# Mainboard.net
KiCad netlist of a schematic drawn in EAGLE
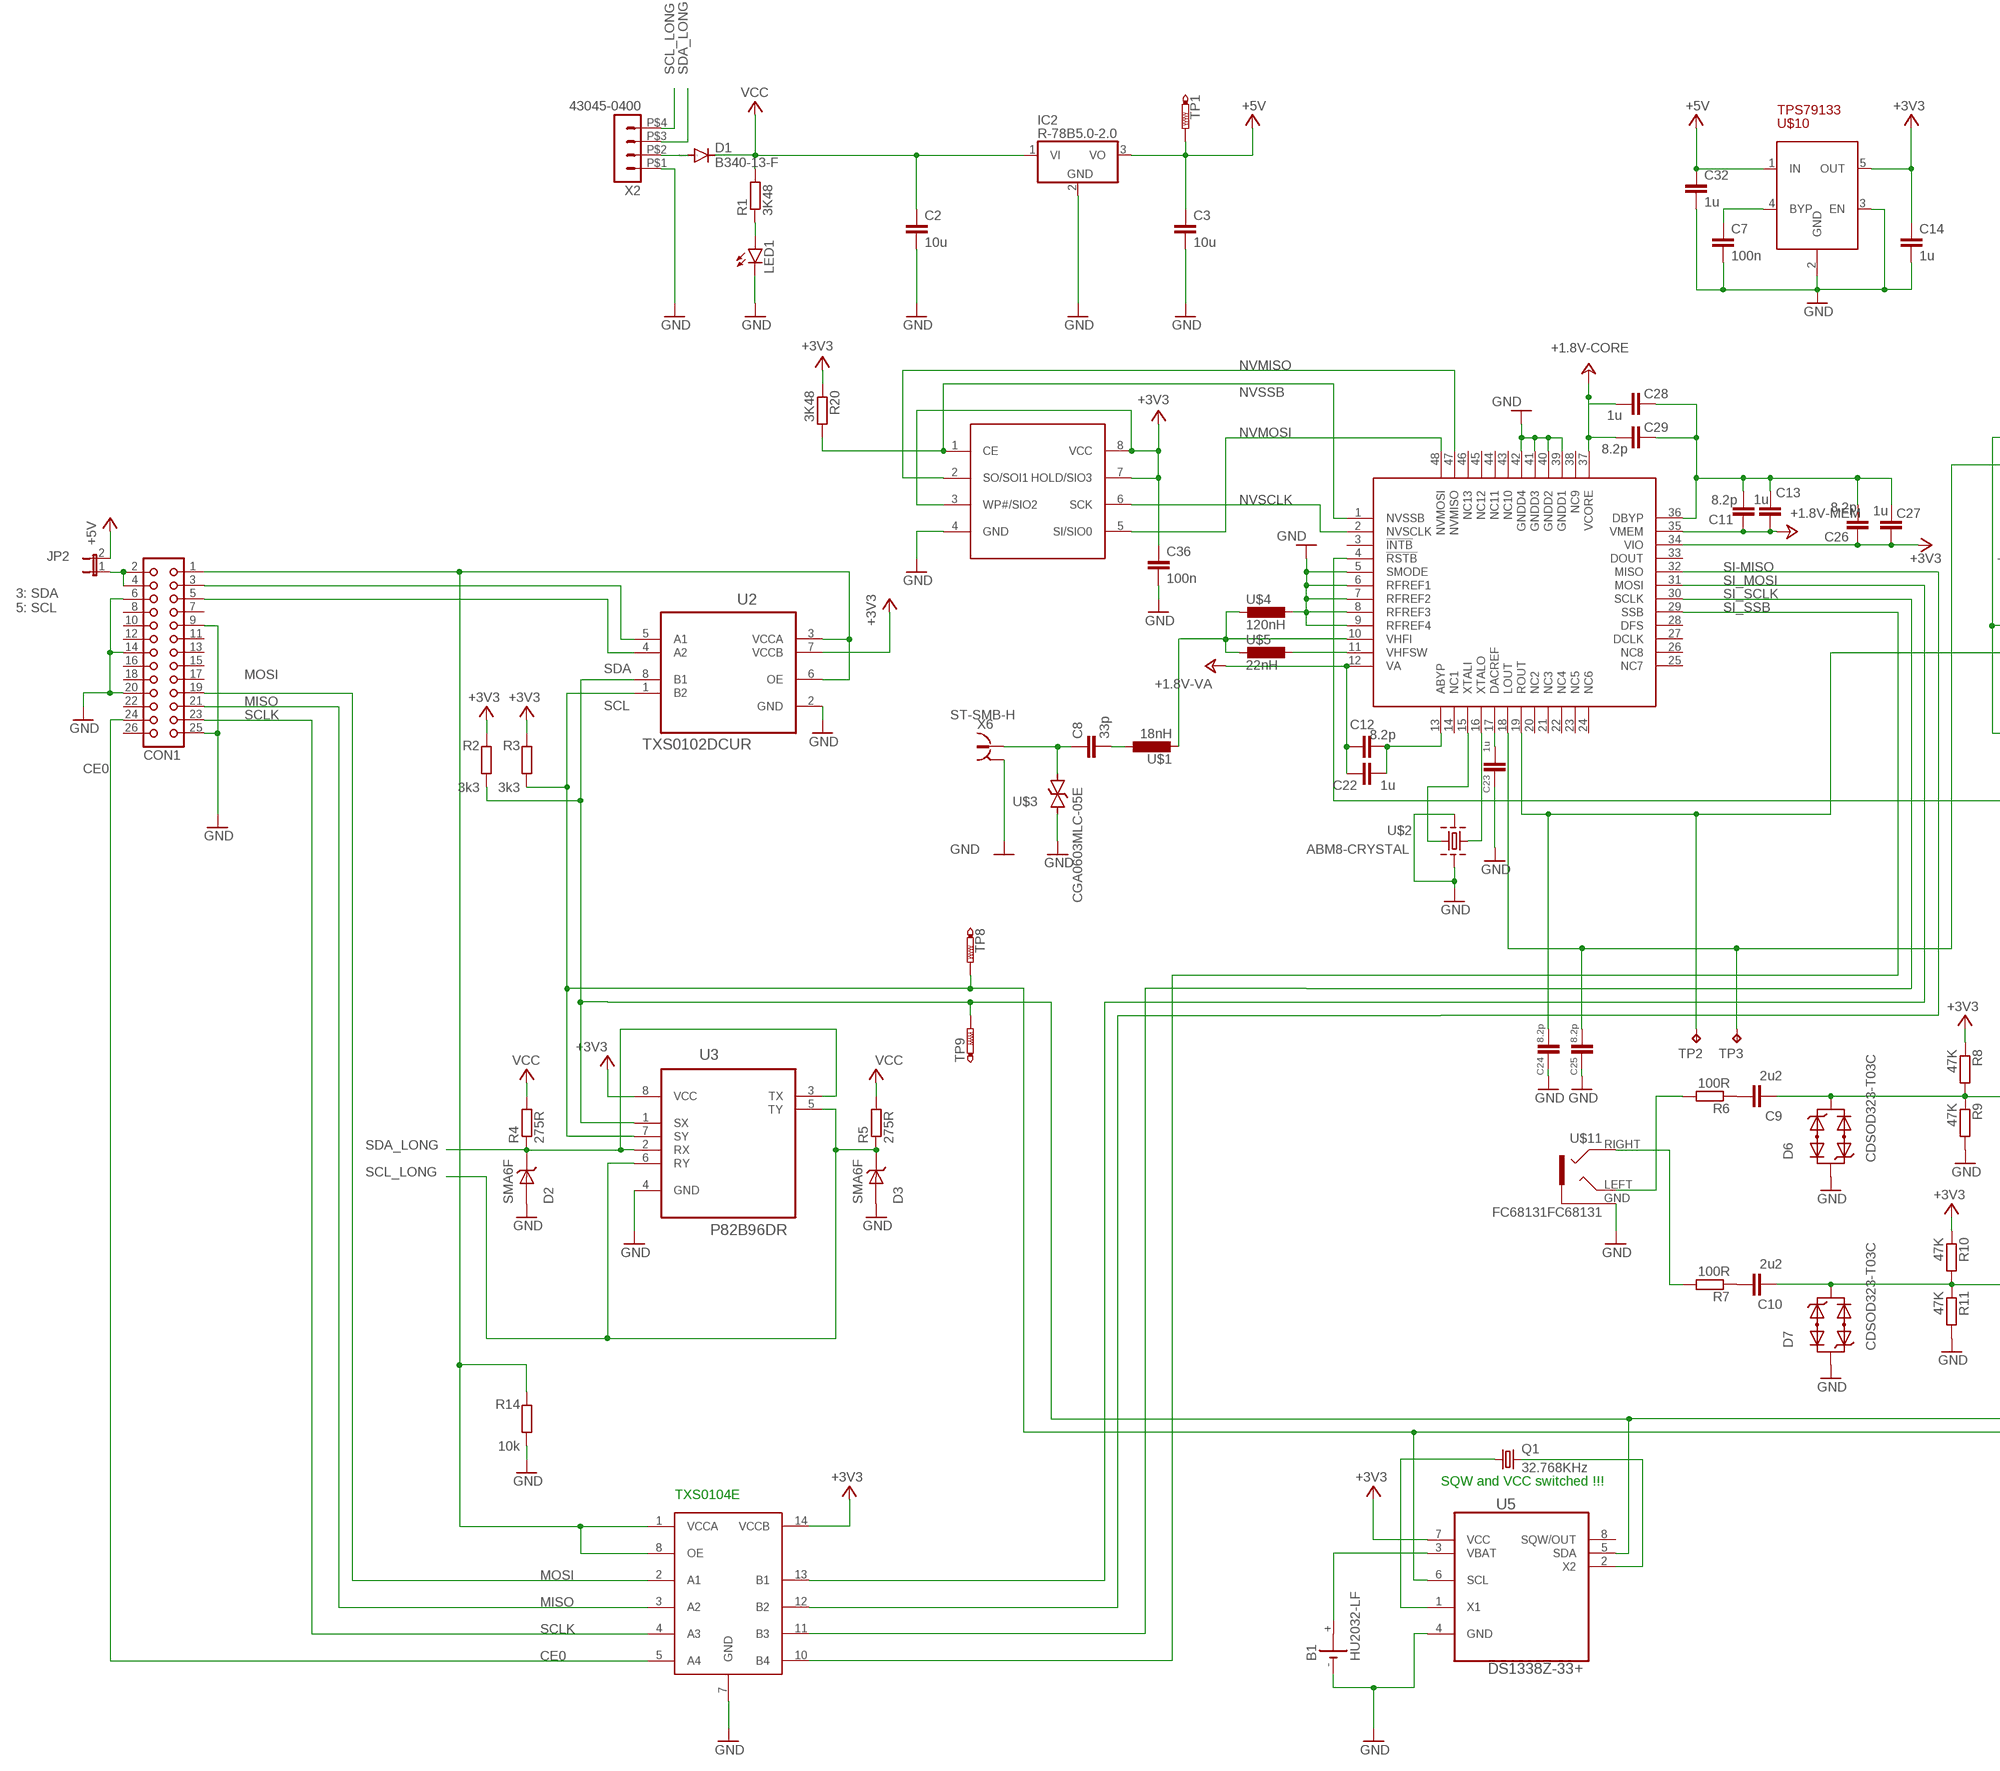
[diagram p0: schematic, sheet 1, part 1 of 3]
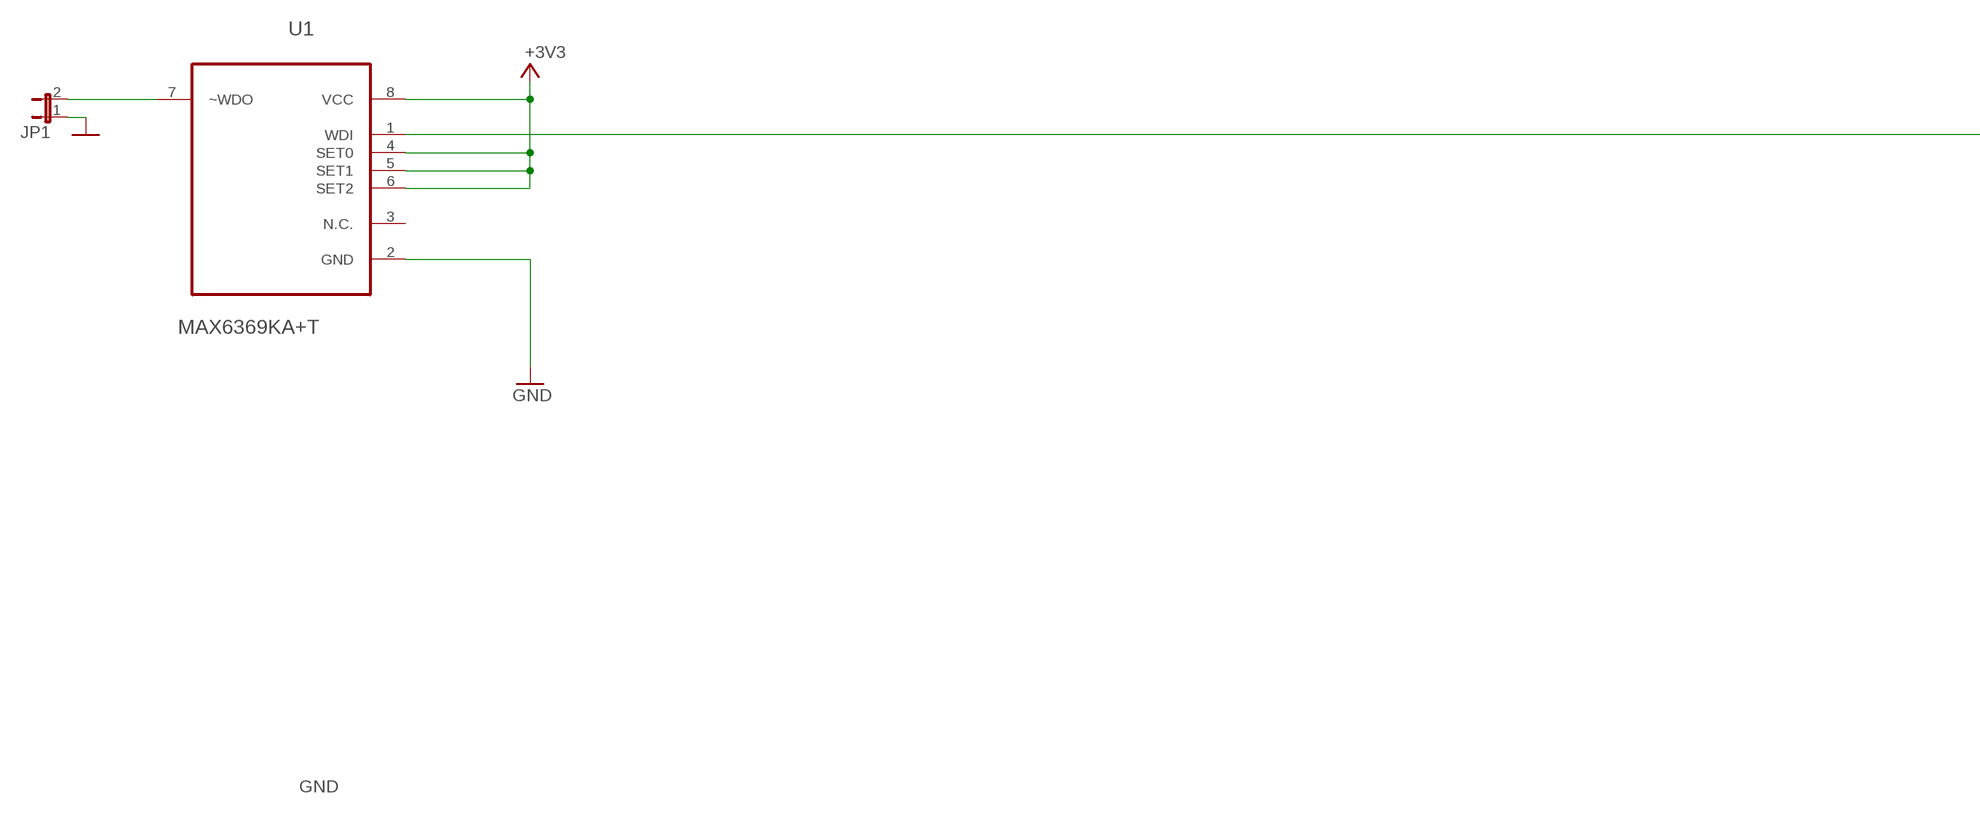
[diagram p1: schematic, sheet 1, part 2 of 3]
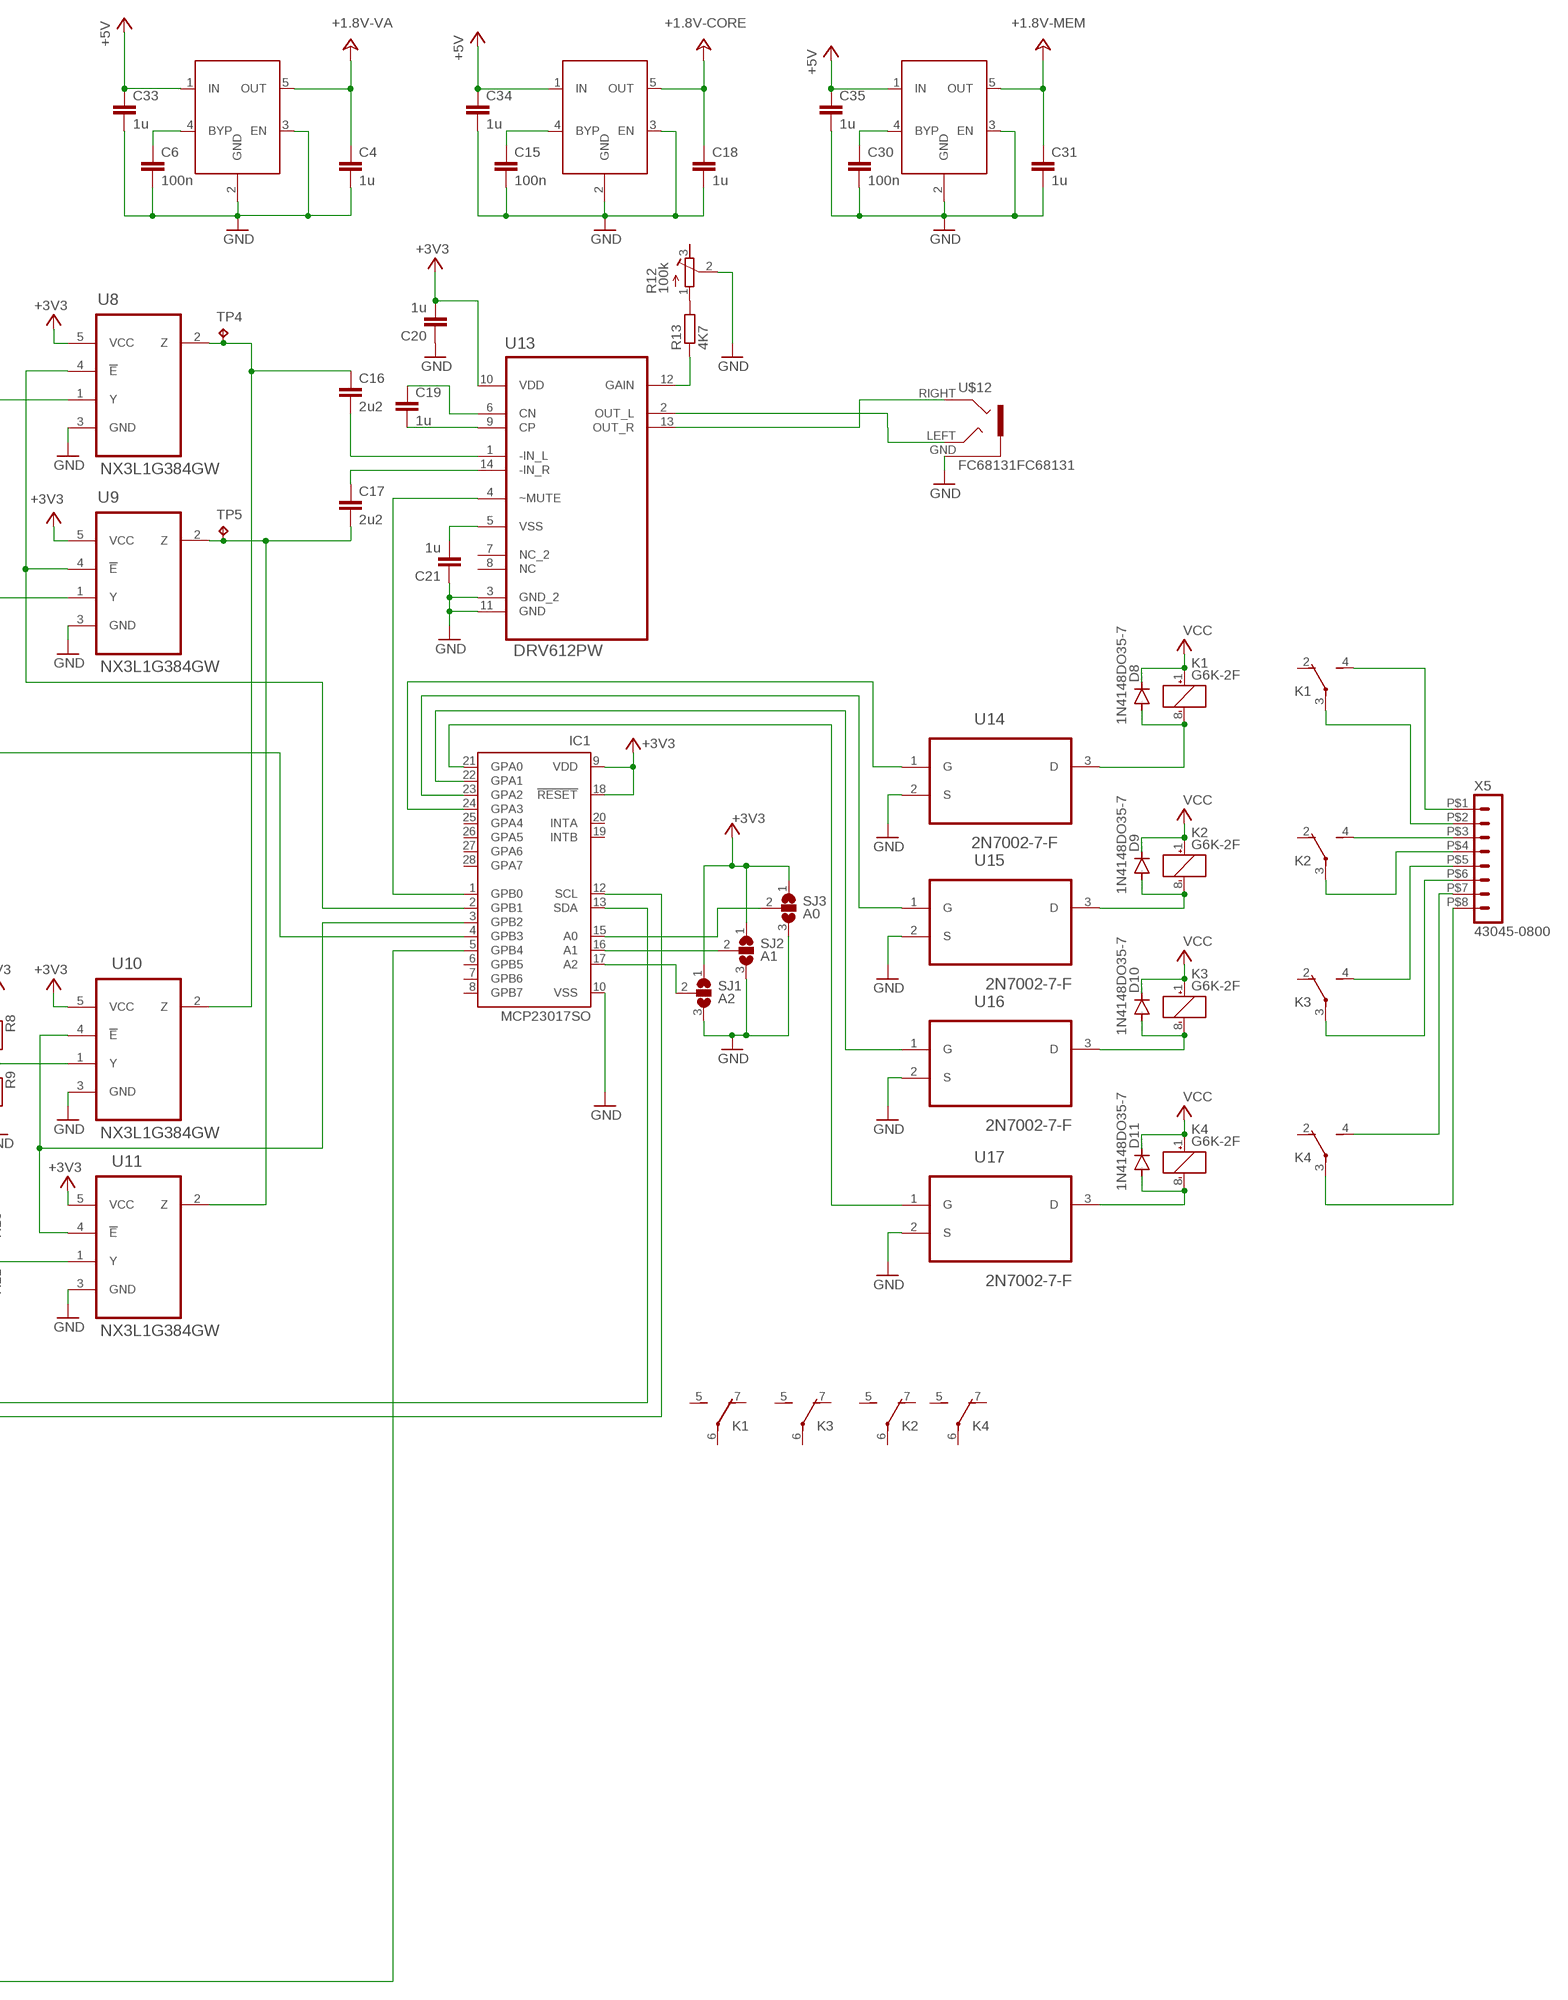
[diagram p2: schematic, sheet 1, part 3 of 3]

(export (version "E")
  (design (tool "Eeschema 10.0.6"))
  (components
    (comp (ref "B1")
      (value "HU2032-LF")
      (footprint "eagle-import:MYCOMPONENTS_HU2032-LF")
      (libsource (lib "eagle-import") (part "MYCOMPONENTS_HU2032-LF"))
    )
    (comp (ref "C2")
      (value "10u")
      (footprint "eagle-import:RCL_C1206")
      (libsource (lib "eagle-import") (part "RCL_C-EUC1206"))
    )
    (comp (ref "C3")
      (value "10u")
      (footprint "eagle-import:RCL_C1206")
      (libsource (lib "eagle-import") (part "RCL_C-EUC1206"))
    )
    (comp (ref "C4")
      (value "1u")
      (footprint "eagle-import:RCL_C0805")
      (libsource (lib "eagle-import") (part "RCL_C-EUC0805"))
    )
    (comp (ref "C6")
      (value "100n")
      (footprint "eagle-import:RCL_C0805")
      (libsource (lib "eagle-import") (part "RCL_C-EUC0805"))
    )
    (comp (ref "C7")
      (value "100n")
      (footprint "eagle-import:RCL_C0805")
      (libsource (lib "eagle-import") (part "RCL_C-EUC0805"))
    )
    (comp (ref "C8")
      (value "33p")
      (footprint "eagle-import:RCL_C0805")
      (libsource (lib "eagle-import") (part "RCL_C-EUC0805"))
    )
    (comp (ref "C9")
      (value "2u2")
      (footprint "eagle-import:RCL_C0805")
      (libsource (lib "eagle-import") (part "RCL_C-EUC0805"))
    )
    (comp (ref "C10")
      (value "2u2")
      (footprint "eagle-import:RCL_C0805")
      (libsource (lib "eagle-import") (part "RCL_C-EUC0805"))
    )
    (comp (ref "C11")
      (value "8.2p")
      (footprint "eagle-import:RCL_C0805")
      (libsource (lib "eagle-import") (part "RCL_C-EUC0805"))
    )
    (comp (ref "C12")
      (value "8.2p")
      (footprint "eagle-import:RCL_C0805")
      (libsource (lib "eagle-import") (part "RCL_C-EUC0805"))
    )
    (comp (ref "C13")
      (value "1u")
      (footprint "eagle-import:RCL_C0805")
      (libsource (lib "eagle-import") (part "RCL_C-EUC0805"))
    )
    (comp (ref "C14")
      (value "1u")
      (footprint "eagle-import:RCL_C0805")
      (libsource (lib "eagle-import") (part "RCL_C-EUC0805"))
    )
    (comp (ref "C15")
      (value "100n")
      (footprint "eagle-import:RCL_C0805")
      (libsource (lib "eagle-import") (part "RCL_C-EUC0805"))
    )
    (comp (ref "C16")
      (value "2u2")
      (footprint "eagle-import:RCL_C0805")
      (libsource (lib "eagle-import") (part "RCL_C-EUC0805"))
    )
    (comp (ref "C17")
      (value "2u2")
      (footprint "eagle-import:RCL_C0805")
      (libsource (lib "eagle-import") (part "RCL_C-EUC0805"))
    )
    (comp (ref "C18")
      (value "1u")
      (footprint "eagle-import:RCL_C0805")
      (libsource (lib "eagle-import") (part "RCL_C-EUC0805"))
    )
    (comp (ref "C19")
      (value "1u")
      (footprint "eagle-import:RCL_C1005")
      (libsource (lib "eagle-import") (part "RCL_C-EUC1005"))
    )
    (comp (ref "C20")
      (value "1u")
      (footprint "eagle-import:RCL_C1005")
      (libsource (lib "eagle-import") (part "RCL_C-EUC1005"))
    )
    (comp (ref "C21")
      (value "1u")
      (footprint "eagle-import:RCL_C1005")
      (libsource (lib "eagle-import") (part "RCL_C-EUC1005"))
    )
    (comp (ref "C22")
      (value "1u")
      (footprint "eagle-import:RCL_C0805")
      (libsource (lib "eagle-import") (part "RCL_C-EUC0805"))
    )
    (comp (ref "C23")
      (value "1u")
      (footprint "eagle-import:RCL_C0805")
      (libsource (lib "eagle-import") (part "RCL_C-EUC0805"))
    )
    (comp (ref "C24")
      (value "8.2p")
      (footprint "eagle-import:RCL_C0805")
      (libsource (lib "eagle-import") (part "RCL_C-EUC0805"))
    )
    (comp (ref "C25")
      (value "8.2p")
      (footprint "eagle-import:RCL_C0805")
      (libsource (lib "eagle-import") (part "RCL_C-EUC0805"))
    )
    (comp (ref "C26")
      (value "8.2p")
      (footprint "eagle-import:RCL_C0805")
      (libsource (lib "eagle-import") (part "RCL_C-EUC0805"))
    )
    (comp (ref "C27")
      (value "1u")
      (footprint "eagle-import:RCL_C0805")
      (libsource (lib "eagle-import") (part "RCL_C-EUC0805"))
    )
    (comp (ref "C28")
      (value "1u")
      (footprint "eagle-import:RCL_C0805")
      (libsource (lib "eagle-import") (part "RCL_C-EUC0805"))
    )
    (comp (ref "C29")
      (value "8.2p")
      (footprint "eagle-import:RCL_C0805")
      (libsource (lib "eagle-import") (part "RCL_C-EUC0805"))
    )
    (comp (ref "C30")
      (value "100n")
      (footprint "eagle-import:RCL_C0805")
      (libsource (lib "eagle-import") (part "RCL_C-EUC0805"))
    )
    (comp (ref "C31")
      (value "1u")
      (footprint "eagle-import:RCL_C0805")
      (libsource (lib "eagle-import") (part "RCL_C-EUC0805"))
    )
    (comp (ref "C32")
      (value "1u")
      (footprint "eagle-import:RCL_C0805")
      (libsource (lib "eagle-import") (part "RCL_C-EUC0805"))
    )
    (comp (ref "C33")
      (value "1u")
      (footprint "eagle-import:RCL_C0805")
      (libsource (lib "eagle-import") (part "RCL_C-EUC0805"))
    )
    (comp (ref "C34")
      (value "1u")
      (footprint "eagle-import:RCL_C0805")
      (libsource (lib "eagle-import") (part "RCL_C-EUC0805"))
    )
    (comp (ref "C35")
      (value "1u")
      (footprint "eagle-import:RCL_C0805")
      (libsource (lib "eagle-import") (part "RCL_C-EUC0805"))
    )
    (comp (ref "C36")
      (value "100n")
      (footprint "eagle-import:RCL_C0805")
      (libsource (lib "eagle-import") (part "RCL_C-EUC0805"))
    )
    (comp (ref "CON1")
      (value "CON26")
      (footprint "eagle-import:CON26")
      (libsource (lib "eagle-import") (part "CON26"))
    )
    (comp (ref "D1")
      (value "B340-13-F")
      (footprint "eagle-import:DIODE_DO-214AC")
      (libsource (lib "eagle-import") (part "DIODE_DIODE-DO-214AC"))
    )
    (comp (ref "D2")
      (value "SMA6F")
      (footprint "eagle-import:MYCOMPONENTS_DO-221AC")
      (libsource (lib "eagle-import") (part "MYCOMPONENTS_SMA6F"))
    )
    (comp (ref "D3")
      (value "SMA6F")
      (footprint "eagle-import:MYCOMPONENTS_DO-221AC")
      (libsource (lib "eagle-import") (part "MYCOMPONENTS_SMA6F"))
    )
    (comp (ref "D6")
      (value "CDSOD323-T03C")
      (footprint "eagle-import:MYCOMPONENTS_SOD323")
      (libsource (lib "eagle-import") (part "MYCOMPONENTS_CDSOD323-T03C"))
    )
    (comp (ref "D7")
      (value "CDSOD323-T03C")
      (footprint "eagle-import:MYCOMPONENTS_SOD323")
      (libsource (lib "eagle-import") (part "MYCOMPONENTS_CDSOD323-T03C"))
    )
    (comp (ref "D8")
      (value "1N4148DO35-7")
      (footprint "eagle-import:DIODE_DO35-7")
      (libsource (lib "eagle-import") (part "DIODE_1N4148DO35-7"))
    )
    (comp (ref "D9")
      (value "1N4148DO35-7")
      (footprint "eagle-import:DIODE_DO35-7")
      (libsource (lib "eagle-import") (part "DIODE_1N4148DO35-7"))
    )
    (comp (ref "D10")
      (value "1N4148DO35-7")
      (footprint "eagle-import:DIODE_DO35-7")
      (libsource (lib "eagle-import") (part "DIODE_1N4148DO35-7"))
    )
    (comp (ref "D11")
      (value "1N4148DO35-7")
      (footprint "eagle-import:DIODE_DO35-7")
      (libsource (lib "eagle-import") (part "DIODE_1N4148DO35-7"))
    )
    (comp (ref "IC1")
      (value "MCP23017SO")
      (footprint "eagle-import:MICROCHIP_SO28W")
      (fields (field (name "MF") "MICROCHIP") (field (name "MPN") "MCP23017-E/SO"))
      (libsource (lib "eagle-import") (part "MICROCHIP_MCP23017SO"))
    )
    (comp (ref "IC2")
      (value "R-78B5.0-2.0")
      (footprint "eagle-import:TO220V")
      (libsource (lib "eagle-import") (part "78TV05"))
    )
    (comp (ref "JP1")
      (value "JUMPER_JP1E")
      (footprint "eagle-import:JUMPER_JP1")
      (libsource (lib "eagle-import") (part "JUMPER_JP1E"))
    )
    (comp (ref "JP2")
      (value "JUMPER_JP1E")
      (footprint "eagle-import:JUMPER_JP1")
      (libsource (lib "eagle-import") (part "JUMPER_JP1E"))
    )
    (comp (ref "K1")
      (value "G6K-2F")
      (footprint "eagle-import:RELAY_G6K-2F")
      (fields (field (name "MF") "OMRON COMPONENTS USA") (field (name "MPN") "G6K-2F DC24"))
      (libsource (lib "eagle-import") (part "RELAY_G6K-2F"))
    )
    (comp (ref "K2")
      (value "G6K-2F")
      (footprint "eagle-import:RELAY_G6K-2F")
      (fields (field (name "MF") "OMRON COMPONENTS USA") (field (name "MPN") "G6K-2F DC24"))
      (libsource (lib "eagle-import") (part "RELAY_G6K-2F"))
    )
    (comp (ref "K3")
      (value "G6K-2F")
      (footprint "eagle-import:RELAY_G6K-2F")
      (fields (field (name "MF") "OMRON COMPONENTS USA") (field (name "MPN") "G6K-2F DC24"))
      (libsource (lib "eagle-import") (part "RELAY_G6K-2F"))
    )
    (comp (ref "K4")
      (value "G6K-2F")
      (footprint "eagle-import:RELAY_G6K-2F")
      (fields (field (name "MF") "OMRON COMPONENTS USA") (field (name "MPN") "G6K-2F DC24"))
      (libsource (lib "eagle-import") (part "RELAY_G6K-2F"))
    )
    (comp (ref "LED1")
      (value "LEDCHIP-LED0805")
      (footprint "eagle-import:CHIP-LED0805")
      (libsource (lib "eagle-import") (part "LEDCHIP-LED0805"))
    )
    (comp (ref "Q1")
      (value "32.768KHz")
      (footprint "eagle-import:CRYSTAL_TC26V")
      (libsource (lib "eagle-import") (part "CRYSTAL_CRYSTALTC26V"))
    )
    (comp (ref "R1")
      (value "3K48")
      (footprint "eagle-import:M0805")
      (libsource (lib "eagle-import") (part "R-EU_M0805"))
    )
    (comp (ref "R2")
      (value "3k3")
      (footprint "eagle-import:M0805")
      (libsource (lib "eagle-import") (part "R-EU_M0805"))
    )
    (comp (ref "R3")
      (value "3k3")
      (footprint "eagle-import:M0805")
      (libsource (lib "eagle-import") (part "R-EU_M0805"))
    )
    (comp (ref "R4")
      (value "275R")
      (footprint "eagle-import:M0805")
      (libsource (lib "eagle-import") (part "R-EU_M0805"))
    )
    (comp (ref "R5")
      (value "275R")
      (footprint "eagle-import:M0805")
      (libsource (lib "eagle-import") (part "R-EU_M0805"))
    )
    (comp (ref "R6")
      (value "100R")
      (footprint "eagle-import:M0805")
      (libsource (lib "eagle-import") (part "R-EU_M0805"))
    )
    (comp (ref "R7")
      (value "100R")
      (footprint "eagle-import:M0805")
      (libsource (lib "eagle-import") (part "R-EU_M0805"))
    )
    (comp (ref "R8")
      (value "47K")
      (footprint "eagle-import:M0805")
      (libsource (lib "eagle-import") (part "R-EU_M0805"))
    )
    (comp (ref "R9")
      (value "47K")
      (footprint "eagle-import:M0805")
      (libsource (lib "eagle-import") (part "R-EU_M0805"))
    )
    (comp (ref "R10")
      (value "47K")
      (footprint "eagle-import:M0805")
      (libsource (lib "eagle-import") (part "R-EU_M0805"))
    )
    (comp (ref "R11")
      (value "47K")
      (footprint "eagle-import:M0805")
      (libsource (lib "eagle-import") (part "R-EU_M0805"))
    )
    (comp (ref "R12")
      (value "100k")
      (footprint "eagle-import:RESISTOR_RTRIM4G_J")
      (libsource (lib "eagle-import") (part "RESISTOR_R-TRIMM4G/J"))
    )
    (comp (ref "R13")
      (value "4K7")
      (footprint "eagle-import:M0805")
      (libsource (lib "eagle-import") (part "R-EU_M0805"))
    )
    (comp (ref "R14")
      (value "10k")
      (footprint "eagle-import:M0805")
      (libsource (lib "eagle-import") (part "R-EU_M0805"))
    )
    (comp (ref "R20")
      (value "3K48")
      (footprint "eagle-import:M0805")
      (libsource (lib "eagle-import") (part "R-EU_M0805"))
    )
    (comp (ref "SJ1")
      (value "A2")
      (footprint "eagle-import:SJ_2")
      (libsource (lib "eagle-import") (part "SJ2W"))
    )
    (comp (ref "SJ2")
      (value "A1")
      (footprint "eagle-import:SJ_2")
      (libsource (lib "eagle-import") (part "SJ2W"))
    )
    (comp (ref "SJ3")
      (value "A0")
      (footprint "eagle-import:SJ_2")
      (libsource (lib "eagle-import") (part "SJ2W"))
    )
    (comp (ref "SPI")
      (value "TXS0104E")
      (footprint "eagle-import:TEXAS_SOP65P640X120-14N")
      (libsource (lib "eagle-import") (part "TXS0104E"))
    )
    (comp (ref "TP1")
      (value "PTR1PAD1-13")
      (footprint "eagle-import:P1-13")
      (libsource (lib "eagle-import") (part "PTR1PAD1-13"))
    )
    (comp (ref "TP2")
      (value "TESTPAD_TPTP07SQ")
      (footprint "eagle-import:TESTPAD_TP07SQ")
      (libsource (lib "eagle-import") (part "TESTPAD_TPTP07SQ"))
    )
    (comp (ref "TP3")
      (value "TESTPAD_TPTP07SQ")
      (footprint "eagle-import:TESTPAD_TP07SQ")
      (libsource (lib "eagle-import") (part "TESTPAD_TPTP07SQ"))
    )
    (comp (ref "TP4")
      (value "TESTPAD_TPTP07SQ")
      (footprint "eagle-import:TESTPAD_TP07SQ")
      (libsource (lib "eagle-import") (part "TESTPAD_TPTP07SQ"))
    )
    (comp (ref "TP5")
      (value "TESTPAD_TPTP07SQ")
      (footprint "eagle-import:TESTPAD_TP07SQ")
      (libsource (lib "eagle-import") (part "TESTPAD_TPTP07SQ"))
    )
    (comp (ref "TP8")
      (value "PTR1PAD1-13")
      (footprint "eagle-import:P1-13")
      (libsource (lib "eagle-import") (part "PTR1PAD1-13"))
    )
    (comp (ref "TP9")
      (value "PTR1PAD1-13")
      (footprint "eagle-import:P1-13")
      (libsource (lib "eagle-import") (part "PTR1PAD1-13"))
    )
    (comp (ref "U$1")
      (value "18nH")
      (footprint "eagle-import:MAINBOARD_0603")
      (libsource (lib "eagle-import") (part "MAINBOARD_L-0603"))
    )
    (comp (ref "U$2")
      (value "ABM8-CRYSTAL")
      (footprint "eagle-import:ABM8")
      (libsource (lib "eagle-import") (part "ABM8-CRYSTAL"))
    )
    (comp (ref "U$3")
      (value "CGA0603MLC-05E")
      (footprint "eagle-import:MAINBOARD_C0603K")
      (libsource (lib "eagle-import") (part "MAINBOARD_CGA0603MLC-05E"))
    )
    (comp (ref "U$4")
      (value "120nH")
      (footprint "eagle-import:MAINBOARD_0603")
      (libsource (lib "eagle-import") (part "MAINBOARD_L-0603"))
    )
    (comp (ref "U$5")
      (value "22nH")
      (footprint "eagle-import:MAINBOARD_0603")
      (libsource (lib "eagle-import") (part "MAINBOARD_L-0603"))
    )
    (comp (ref "U$6")
      (value "SI4684-MYSMD")
      (footprint "eagle-import:QFN48-SI4684")
      (libsource (lib "eagle-import") (part "SI4684-MYSMD"))
    )
    (comp (ref "U$7")
      (value "TPS79118")
      (footprint "eagle-import:SOT23-5")
      (libsource (lib "eagle-import") (part "TPS79118"))
    )
    (comp (ref "U$8")
      (value "TPS79118")
      (footprint "eagle-import:SOT23-5")
      (libsource (lib "eagle-import") (part "TPS79118"))
    )
    (comp (ref "U$9")
      (value "TPS79118")
      (footprint "eagle-import:SOT23-5")
      (libsource (lib "eagle-import") (part "TPS79118"))
    )
    (comp (ref "U$10")
      (value "TPS79133")
      (footprint "eagle-import:SOT23-5")
      (libsource (lib "eagle-import") (part "TPS79133"))
    )
    (comp (ref "U$11")
      (value "FC68131FC68131")
      (footprint "eagle-import:FC68131")
      (libsource (lib "eagle-import") (part "FC68131FC68131"))
    )
    (comp (ref "U$12")
      (value "FC68131FC68131")
      (footprint "eagle-import:FC68131")
      (libsource (lib "eagle-import") (part "FC68131FC68131"))
    )
    (comp (ref "U$13")
      (value "SST26VF032B")
      (footprint "eagle-import:SOIJ8")
      (libsource (lib "eagle-import") (part "SST26VF032B"))
    )
    (comp (ref "U1")
      (value "MAX6369KA+T")
      (footprint "eagle-import:MAXIM_BY_ELEMENT14_BATCH_1_SOT65P280X145-8N")
      (libsource (lib "eagle-import") (part "MAXIM_BY_ELEMENT14_BATCH_1_MAX6369KA+T"))
    )
    (comp (ref "U2")
      (value "TXS0102DCUR")
      (footprint "eagle-import:TEXAS_SOP50P310X90-8N")
      (libsource (lib "eagle-import") (part "TEXAS_TXS0102DCUR"))
    )
    (comp (ref "U3")
      (value "P82B96DR")
      (footprint "eagle-import:TEXAS_SOIC127P600X175-8N")
      (libsource (lib "eagle-import") (part "TEXAS_P82B96DR"))
    )
    (comp (ref "U5")
      (value "DS1338Z-33+")
      (footprint "eagle-import:MAXIM_BY_ELEMENT14_BATCH_1_SOIC127P600X175-8N")
      (libsource (lib "eagle-import") (part "MAXIM_BY_ELEMENT14_BATCH_1_DS1338Z-33+"))
    )
    (comp (ref "U8")
      (value "NX3L1G384GW")
      (footprint "eagle-import:NXP_BY_ELEMENT14_BATCH_1_SOT65P212X110-5N")
      (libsource (lib "eagle-import") (part "NXP_BY_ELEMENT14_BATCH_1_NX3L1G384GW"))
    )
    (comp (ref "U9")
      (value "NX3L1G384GW")
      (footprint "eagle-import:NXP_BY_ELEMENT14_BATCH_1_SOT65P212X110-5N")
      (libsource (lib "eagle-import") (part "NXP_BY_ELEMENT14_BATCH_1_NX3L1G384GW"))
    )
    (comp (ref "U10")
      (value "NX3L1G384GW")
      (footprint "eagle-import:NXP_BY_ELEMENT14_BATCH_1_SOT65P212X110-5N")
      (libsource (lib "eagle-import") (part "NXP_BY_ELEMENT14_BATCH_1_NX3L1G384GW"))
    )
    (comp (ref "U11")
      (value "NX3L1G384GW")
      (footprint "eagle-import:NXP_BY_ELEMENT14_BATCH_1_SOT65P212X110-5N")
      (libsource (lib "eagle-import") (part "NXP_BY_ELEMENT14_BATCH_1_NX3L1G384GW"))
    )
    (comp (ref "U13")
      (value "DRV612PW")
      (footprint "eagle-import:TEXAS_SOP65P640X120-14N")
      (libsource (lib "eagle-import") (part "TEXAS_DRV612PW"))
    )
    (comp (ref "U14")
      (value "2N7002-7-F")
      (footprint "eagle-import:DIODES_SOT103P240X110-3N")
      (libsource (lib "eagle-import") (part "DIODES_2N7002-7-F"))
    )
    (comp (ref "U15")
      (value "2N7002-7-F")
      (footprint "eagle-import:DIODES_SOT103P240X110-3N")
      (libsource (lib "eagle-import") (part "DIODES_2N7002-7-F"))
    )
    (comp (ref "U16")
      (value "2N7002-7-F")
      (footprint "eagle-import:DIODES_SOT103P240X110-3N")
      (libsource (lib "eagle-import") (part "DIODES_2N7002-7-F"))
    )
    (comp (ref "U17")
      (value "2N7002-7-F")
      (footprint "eagle-import:DIODES_SOT103P240X110-3N")
      (libsource (lib "eagle-import") (part "DIODES_2N7002-7-F"))
    )
    (comp (ref "X2")
      (value "43045-0400")
      (footprint "eagle-import:CON-MOLEX-MICRO-FIT-3_0_43045-0400")
      (libsource (lib "eagle-import") (part "CON-MOLEX-MICRO-FIT-3_0_HEADER_POS4_?43045-0401"))
    )
    (comp (ref "X5")
      (value "43045-0800")
      (footprint "eagle-import:CON-MOLEX-MICRO-FIT-3_0_43045-0800")
      (libsource (lib "eagle-import") (part "CON-MOLEX-MICRO-FIT-3_0_HEADER_POS8_?43045-0800"))
    )
    (comp (ref "X6")
      (value "ST-SMB-H")
      (footprint "eagle-import:MAINBOARD_ST-SMB-H")
      (libsource (lib "eagle-import") (part "MAINBOARD_ST-SMB-H"))
    )
  )
  (nets
    (net (code "1") (name "+1.8V-CORE") (class "Default")
      (node (ref "C18") (pin "1") (pinfunction "1_1") (pintype "passive"))
      (node (ref "C28") (pin "2") (pinfunction "2_2") (pintype "passive"))
      (node (ref "C29") (pin "2") (pinfunction "2_2") (pintype "passive"))
      (node (ref "U$6") (pin "37") (pinfunction "VCORE_37") (pintype "bidirectional"))
      (node (ref "U$8") (pin "5") (pinfunction "OUT_5") (pintype "power_in"))
    )
    (net (code "2") (name "+1.8V-MEM") (class "Default")
      (node (ref "C11") (pin "1") (pinfunction "1_1") (pintype "passive"))
      (node (ref "C13") (pin "1") (pinfunction "1_1") (pintype "passive"))
      (node (ref "C31") (pin "1") (pinfunction "1_1") (pintype "passive"))
      (node (ref "U$6") (pin "35") (pinfunction "VMEM_35") (pintype "bidirectional"))
      (node (ref "U$9") (pin "5") (pinfunction "OUT_5") (pintype "power_in"))
    )
    (net (code "3") (name "+1.8V-VA") (class "Default")
      (node (ref "C12") (pin "1") (pinfunction "1_1") (pintype "passive"))
      (node (ref "C22") (pin "1") (pinfunction "1_1") (pintype "passive"))
      (node (ref "C4") (pin "1") (pinfunction "1_1") (pintype "passive"))
      (node (ref "U$6") (pin "12") (pinfunction "VA_12") (pintype "bidirectional"))
      (node (ref "U$7") (pin "5") (pinfunction "OUT_5") (pintype "power_in"))
    )
    (net (code "4") (name "+3V3") (class "Default")
      (node (ref "C14") (pin "1") (pinfunction "1_1") (pintype "passive"))
      (node (ref "C20") (pin "2") (pinfunction "2_2") (pintype "passive"))
      (node (ref "C26") (pin "1") (pinfunction "1_1") (pintype "passive"))
      (node (ref "C27") (pin "1") (pinfunction "1_1") (pintype "passive"))
      (node (ref "C36") (pin "1") (pinfunction "1_1") (pintype "passive"))
      (node (ref "IC1") (pin "18") (pinfunction "~{RESET}_18") (pintype "input"))
      (node (ref "IC1") (pin "9") (pinfunction "VDD_9") (pintype "power_in"))
      (node (ref "R10") (pin "1") (pinfunction "1_1") (pintype "passive"))
      (node (ref "R2") (pin "2") (pinfunction "2_2") (pintype "passive"))
      (node (ref "R20") (pin "1") (pinfunction "1_1") (pintype "passive"))
      (node (ref "R3") (pin "2") (pinfunction "2_2") (pintype "passive"))
      (node (ref "R8") (pin "1") (pinfunction "1_1") (pintype "passive"))
      (node (ref "SJ1") (pin "1") (pinfunction "1_1") (pintype "passive"))
      (node (ref "SJ2") (pin "1") (pinfunction "1_1") (pintype "passive"))
      (node (ref "SJ3") (pin "1") (pinfunction "1_1") (pintype "passive"))
      (node (ref "SPI") (pin "14") (pinfunction "VCCB_14") (pintype "bidirectional"))
      (node (ref "U$10") (pin "5") (pinfunction "OUT_5") (pintype "power_in"))
      (node (ref "U$13") (pin "3") (pinfunction "WP#/SIO2_3") (pintype "bidirectional"))
      (node (ref "U$13") (pin "7") (pinfunction "HOLD/SIO3_7") (pintype "bidirectional"))
      (node (ref "U$13") (pin "8") (pinfunction "VCC_8") (pintype "power_in"))
      (node (ref "U$6") (pin "34") (pinfunction "VIO_34") (pintype "bidirectional"))
      (node (ref "U1") (pin "4") (pinfunction "SET0_4") (pintype "input"))
      (node (ref "U1") (pin "5") (pinfunction "SET1_5") (pintype "input"))
      (node (ref "U1") (pin "6") (pinfunction "SET2_6") (pintype "input"))
      (node (ref "U1") (pin "8") (pinfunction "VCC_8") (pintype "power_in"))
      (node (ref "U10") (pin "5") (pinfunction "VCC_5") (pintype "power_in"))
      (node (ref "U11") (pin "5") (pinfunction "VCC_5") (pintype "power_in"))
      (node (ref "U13") (pin "10") (pinfunction "VDD_10") (pintype "power_in"))
      (node (ref "U2") (pin "7") (pinfunction "VCCB_7") (pintype "power_in"))
      (node (ref "U3") (pin "8") (pinfunction "VCC_8") (pintype "power_in"))
      (node (ref "U5") (pin "7") (pinfunction "VCC_7") (pintype "power_in"))
      (node (ref "U8") (pin "5") (pinfunction "VCC_5") (pintype "power_in"))
      (node (ref "U9") (pin "5") (pinfunction "VCC_5") (pintype "power_in"))
    )
    (net (code "5") (name "+5V") (class "Default")
      (node (ref "C3") (pin "1") (pinfunction "1_1") (pintype "passive"))
      (node (ref "C32") (pin "1") (pinfunction "1_1") (pintype "passive"))
      (node (ref "C33") (pin "1") (pinfunction "1_1") (pintype "passive"))
      (node (ref "C34") (pin "1") (pinfunction "1_1") (pintype "passive"))
      (node (ref "C35") (pin "1") (pinfunction "1_1") (pintype "passive"))
      (node (ref "IC2") (pin "3") (pinfunction "VO_3") (pintype "passive"))
      (node (ref "JP2") (pin "2") (pinfunction "2_2") (pintype "passive"))
      (node (ref "TP1") (pin "TP") (pinfunction "TP_TP") (pintype "input"))
      (node (ref "U$10") (pin "1") (pinfunction "IN_1") (pintype "power_in"))
      (node (ref "U$7") (pin "1") (pinfunction "IN_1") (pintype "power_in"))
      (node (ref "U$8") (pin "1") (pinfunction "IN_1") (pintype "power_in"))
      (node (ref "U$9") (pin "1") (pinfunction "IN_1") (pintype "power_in"))
    )
    (net (code "6") (name "/CE0") (class "Default")
      (node (ref "CON1") (pin "24") (pinfunction "24_24") (pintype "passive"))
      (node (ref "SPI") (pin "5") (pinfunction "A4_5") (pintype "bidirectional"))
    )
    (net (code "7") (name "/MISO") (class "Default")
      (node (ref "CON1") (pin "21") (pinfunction "21_21") (pintype "passive"))
      (node (ref "SPI") (pin "3") (pinfunction "A2_3") (pintype "bidirectional"))
    )
    (net (code "8") (name "/MOSI") (class "Default")
      (node (ref "CON1") (pin "19") (pinfunction "19_19") (pintype "passive"))
      (node (ref "SPI") (pin "2") (pinfunction "A1_2") (pintype "bidirectional"))
    )
    (net (code "9") (name "/NVMISO") (class "Default")
      (node (ref "U$13") (pin "2") (pinfunction "SO/SOI1_2") (pintype "bidirectional"))
      (node (ref "U$6") (pin "47") (pinfunction "NVMISO_47") (pintype "bidirectional"))
    )
    (net (code "10") (name "/NVMOSI") (class "Default")
      (node (ref "U$13") (pin "5") (pinfunction "SI/SIO0_5") (pintype "bidirectional"))
      (node (ref "U$6") (pin "48") (pinfunction "NVMOSI_48") (pintype "bidirectional"))
    )
    (net (code "11") (name "/NVSCLK") (class "Default")
      (node (ref "U$13") (pin "6") (pinfunction "SCK_6") (pintype "bidirectional"))
      (node (ref "U$6") (pin "2") (pinfunction "NVSCLK_2") (pintype "bidirectional"))
    )
    (net (code "12") (name "/NVSSB") (class "Default")
      (node (ref "R20") (pin "2") (pinfunction "2_2") (pintype "passive"))
      (node (ref "U$13") (pin "1") (pinfunction "CE_1") (pintype "bidirectional"))
      (node (ref "U$6") (pin "1") (pinfunction "NVSSB_1") (pintype "bidirectional"))
    )
    (net (code "13") (name "/SCLK") (class "Default")
      (node (ref "CON1") (pin "23") (pinfunction "23_23") (pintype "passive"))
      (node (ref "SPI") (pin "4") (pinfunction "A3_4") (pintype "bidirectional"))
    )
    (net (code "14") (name "/SCL_LONG") (class "Default")
      (node (ref "D3") (pin "KAT") (pinfunction "KAT_KAT") (pintype "bidirectional"))
      (node (ref "R5") (pin "1") (pinfunction "1_1") (pintype "passive"))
      (node (ref "U3") (pin "5") (pinfunction "TY_5") (pintype "output"))
      (node (ref "U3") (pin "6") (pinfunction "RY_6") (pintype "input"))
      (node (ref "X2") (pin "P$4") (pinfunction "4_P$4") (pintype "passive"))
    )
    (net (code "15") (name "/SDA_LONG") (class "Default")
      (node (ref "D2") (pin "KAT") (pinfunction "KAT_KAT") (pintype "bidirectional"))
      (node (ref "R4") (pin "1") (pinfunction "1_1") (pintype "passive"))
      (node (ref "U3") (pin "2") (pinfunction "RX_2") (pintype "input"))
      (node (ref "U3") (pin "3") (pinfunction "TX_3") (pintype "output"))
      (node (ref "X2") (pin "P$3") (pinfunction "3_P$3") (pintype "passive"))
    )
    (net (code "16") (name "/SI-MISO") (class "Default")
      (node (ref "SPI") (pin "12") (pinfunction "B2_12") (pintype "bidirectional"))
      (node (ref "U$6") (pin "32") (pinfunction "MISO_32") (pintype "bidirectional"))
    )
    (net (code "17") (name "/SI_MOSI") (class "Default")
      (node (ref "SPI") (pin "13") (pinfunction "B1_13") (pintype "bidirectional"))
      (node (ref "U$6") (pin "31") (pinfunction "MOSI_31") (pintype "bidirectional"))
    )
    (net (code "18") (name "/SI_SCLK") (class "Default")
      (node (ref "SPI") (pin "11") (pinfunction "B3_11") (pintype "bidirectional"))
      (node (ref "U$6") (pin "30") (pinfunction "SCLK_30") (pintype "bidirectional"))
    )
    (net (code "19") (name "/SI_SSB") (class "Default")
      (node (ref "SPI") (pin "10") (pinfunction "B4_10") (pintype "bidirectional"))
      (node (ref "U$6") (pin "29") (pinfunction "SSB_29") (pintype "bidirectional"))
    )
    (net (code "20") (name "GND") (class "Default")
      (node (ref "B1") (pin "-") (pinfunction "-_-") (pintype "passive"))
      (node (ref "C14") (pin "2") (pinfunction "2_2") (pintype "passive"))
      (node (ref "C15") (pin "2") (pinfunction "2_2") (pintype "passive"))
      (node (ref "C18") (pin "2") (pinfunction "2_2") (pintype "passive"))
      (node (ref "C2") (pin "2") (pinfunction "2_2") (pintype "passive"))
      (node (ref "C20") (pin "1") (pinfunction "1_1") (pintype "passive"))
      (node (ref "C21") (pin "1") (pinfunction "1_1") (pintype "passive"))
      (node (ref "C23") (pin "1") (pinfunction "1_1") (pintype "passive"))
      (node (ref "C24") (pin "1") (pinfunction "1_1") (pintype "passive"))
      (node (ref "C25") (pin "1") (pinfunction "1_1") (pintype "passive"))
      (node (ref "C3") (pin "2") (pinfunction "2_2") (pintype "passive"))
      (node (ref "C30") (pin "2") (pinfunction "2_2") (pintype "passive"))
      (node (ref "C31") (pin "2") (pinfunction "2_2") (pintype "passive"))
      (node (ref "C32") (pin "2") (pinfunction "2_2") (pintype "passive"))
      (node (ref "C33") (pin "2") (pinfunction "2_2") (pintype "passive"))
      (node (ref "C34") (pin "2") (pinfunction "2_2") (pintype "passive"))
      (node (ref "C35") (pin "2") (pinfunction "2_2") (pintype "passive"))
      (node (ref "C36") (pin "2") (pinfunction "2_2") (pintype "passive"))
      (node (ref "C4") (pin "2") (pinfunction "2_2") (pintype "passive"))
      (node (ref "C6") (pin "2") (pinfunction "2_2") (pintype "passive"))
      (node (ref "C7") (pin "2") (pinfunction "2_2") (pintype "passive"))
      (node (ref "CON1") (pin "14") (pinfunction "14_14") (pintype "passive"))
      (node (ref "CON1") (pin "20") (pinfunction "20_20") (pintype "passive"))
      (node (ref "CON1") (pin "25") (pinfunction "25_25") (pintype "passive"))
      (node (ref "CON1") (pin "6") (pinfunction "6_6") (pintype "passive"))
      (node (ref "CON1") (pin "9") (pinfunction "9_9") (pintype "passive"))
      (node (ref "D2") (pin "AN") (pinfunction "AN_AN") (pintype "bidirectional"))
      (node (ref "D3") (pin "AN") (pinfunction "AN_AN") (pintype "bidirectional"))
      (node (ref "D6") (pin "P$1") (pinfunction "P$1_P$1") (pintype "bidirectional"))
      (node (ref "D7") (pin "P$1") (pinfunction "P$1_P$1") (pintype "bidirectional"))
      (node (ref "IC1") (pin "10") (pinfunction "VSS_10") (pintype "power_in"))
      (node (ref "IC2") (pin "2") (pinfunction "GND_2") (pintype "passive"))
      (node (ref "JP1") (pin "1") (pinfunction "1_1") (pintype "passive"))
      (node (ref "LED1") (pin "C") (pinfunction "C_C") (pintype "passive"))
      (node (ref "R11") (pin "2") (pinfunction "2_2") (pintype "passive"))
      (node (ref "R12") (pin "2") (pinfunction "S_2") (pintype "passive"))
      (node (ref "R14") (pin "1") (pinfunction "1_1") (pintype "passive"))
      (node (ref "R9") (pin "2") (pinfunction "2_2") (pintype "passive"))
      (node (ref "SJ1") (pin "3") (pinfunction "3_3") (pintype "passive"))
      (node (ref "SJ2") (pin "3") (pinfunction "3_3") (pintype "passive"))
      (node (ref "SJ3") (pin "3") (pinfunction "3_3") (pintype "passive"))
      (node (ref "SPI") (pin "7") (pinfunction "GND_7") (pintype "bidirectional"))
      (node (ref "U$10") (pin "2") (pinfunction "GND_2") (pintype "power_in"))
      (node (ref "U$10") (pin "3") (pinfunction "EN_3") (pintype "bidirectional"))
      (node (ref "U$11") (pin "GND") (pinfunction "GND_GND") (pintype "passive"))
      (node (ref "U$12") (pin "GND") (pinfunction "GND_GND") (pintype "passive"))
      (node (ref "U$13") (pin "4") (pinfunction "GND_4") (pintype "power_in"))
      (node (ref "U$2") (pin "1") (pinfunction "GND1_1") (pintype "bidirectional"))
      (node (ref "U$2") (pin "3") (pinfunction "GND2_3") (pintype "bidirectional"))
      (node (ref "U$3") (pin "1") (pinfunction "1_1") (pintype "passive"))
      (node (ref "U$4") (pin "1") (pinfunction "1_1") (pintype "passive"))
      (node (ref "U$6") (pin "39") (pinfunction "GNDD1_39") (pintype "bidirectional"))
      (node (ref "U$6") (pin "40") (pinfunction "GNDD2_40") (pintype "bidirectional"))
      (node (ref "U$6") (pin "41") (pinfunction "GNDD3_41") (pintype "bidirectional"))
      (node (ref "U$6") (pin "42") (pinfunction "GNDD4_42") (pintype "bidirectional"))
      (node (ref "U$6") (pin "5") (pinfunction "SMODE_5") (pintype "bidirectional"))
      (node (ref "U$6") (pin "6") (pinfunction "RFREF1_6") (pintype "bidirectional"))
      (node (ref "U$6") (pin "7") (pinfunction "RFREF2_7") (pintype "bidirectional"))
      (node (ref "U$6") (pin "8") (pinfunction "RFREF3_8") (pintype "bidirectional"))
      (node (ref "U$6") (pin "9") (pinfunction "RFREF4_9") (pintype "bidirectional"))
      (node (ref "U$7") (pin "2") (pinfunction "GND_2") (pintype "power_in"))
      (node (ref "U$7") (pin "3") (pinfunction "EN_3") (pintype "bidirectional"))
      (node (ref "U$8") (pin "2") (pinfunction "GND_2") (pintype "power_in"))
      (node (ref "U$8") (pin "3") (pinfunction "EN_3") (pintype "bidirectional"))
      (node (ref "U$9") (pin "2") (pinfunction "GND_2") (pintype "power_in"))
      (node (ref "U$9") (pin "3") (pinfunction "EN_3") (pintype "bidirectional"))
      (node (ref "U1") (pin "2") (pinfunction "GND_2") (pintype "passive"))
      (node (ref "U10") (pin "3") (pinfunction "GND_3") (pintype "passive"))
      (node (ref "U11") (pin "3") (pinfunction "GND_3") (pintype "passive"))
      (node (ref "U13") (pin "11") (pinfunction "GND_11") (pintype "passive"))
      (node (ref "U13") (pin "3") (pinfunction "GND_2_3") (pintype "passive"))
      (node (ref "U14") (pin "2") (pinfunction "S_2") (pintype "passive"))
      (node (ref "U15") (pin "2") (pinfunction "S_2") (pintype "passive"))
      (node (ref "U16") (pin "2") (pinfunction "S_2") (pintype "passive"))
      (node (ref "U17") (pin "2") (pinfunction "S_2") (pintype "passive"))
      (node (ref "U2") (pin "2") (pinfunction "GND_2") (pintype "passive"))
      (node (ref "U3") (pin "4") (pinfunction "GND_4") (pintype "passive"))
      (node (ref "U5") (pin "4") (pinfunction "GND_4") (pintype "passive"))
      (node (ref "U8") (pin "3") (pinfunction "GND_3") (pintype "passive"))
      (node (ref "U9") (pin "3") (pinfunction "GND_3") (pintype "passive"))
      (node (ref "X2") (pin "P$1") (pinfunction "1_P$1") (pintype "passive"))
      (node (ref "X6") (pin "2") (pinfunction "2_2") (pintype "passive"))
      (node (ref "X6") (pin "3") (pinfunction "2_3") (pintype "passive"))
      (node (ref "X6") (pin "4") (pinfunction "2_4") (pintype "passive"))
      (node (ref "X6") (pin "5") (pinfunction "2_5") (pintype "passive"))
    )
    (net (code "21") (name "Net-(C8-Pad1)") (class "Default")
      (node (ref "C8") (pin "1") (pinfunction "1_1") (pintype "passive"))
      (node (ref "U$3") (pin "2") (pinfunction "2_2") (pintype "passive"))
      (node (ref "X6") (pin "1") (pinfunction "1_1") (pintype "passive"))
    )
    (net (code "22") (name "Net-(C8-Pad2)") (class "Default")
      (node (ref "C8") (pin "2") (pinfunction "2_2") (pintype "passive"))
      (node (ref "U$1") (pin "1") (pinfunction "1_1") (pintype "passive"))
    )
    (net (code "23") (name "Net-(C9-Pad1)") (class "Default")
      (node (ref "C9") (pin "1") (pinfunction "1_1") (pintype "passive"))
      (node (ref "R6") (pin "1") (pinfunction "1_1") (pintype "passive"))
    )
    (net (code "24") (name "Net-(C10-Pad1)") (class "Default")
      (node (ref "C10") (pin "1") (pinfunction "1_1") (pintype "passive"))
      (node (ref "R7") (pin "1") (pinfunction "1_1") (pintype "passive"))
    )
    (net (code "25") (name "Net-(CON1-Pad2)") (class "Default")
      (node (ref "CON1") (pin "2") (pinfunction "2_2") (pintype "passive"))
      (node (ref "CON1") (pin "4") (pinfunction "4_4") (pintype "passive"))
      (node (ref "JP2") (pin "1") (pinfunction "1_1") (pintype "passive"))
    )
    (net (code "26") (name "Net-(IC1-A0)") (class "Default")
      (node (ref "IC1") (pin "15") (pinfunction "A0_15") (pintype "input"))
      (node (ref "SJ3") (pin "2") (pinfunction "2_2") (pintype "passive"))
    )
    (net (code "27") (name "Net-(IC1-A1)") (class "Default")
      (node (ref "IC1") (pin "16") (pinfunction "A1_16") (pintype "input"))
      (node (ref "SJ2") (pin "2") (pinfunction "2_2") (pintype "passive"))
    )
    (net (code "28") (name "Net-(IC1-A2)") (class "Default")
      (node (ref "IC1") (pin "17") (pinfunction "A2_17") (pintype "input"))
      (node (ref "SJ1") (pin "2") (pinfunction "2_2") (pintype "passive"))
    )
    (net (code "29") (name "Net-(IC1-GPA0)") (class "Default")
      (node (ref "IC1") (pin "21") (pinfunction "GPA0_21") (pintype "bidirectional"))
      (node (ref "U17") (pin "1") (pinfunction "G_1") (pintype "input"))
    )
    (net (code "30") (name "Net-(IC1-GPA1)") (class "Default")
      (node (ref "IC1") (pin "22") (pinfunction "GPA1_22") (pintype "bidirectional"))
      (node (ref "U16") (pin "1") (pinfunction "G_1") (pintype "input"))
    )
    (net (code "31") (name "Net-(IC1-GPA2)") (class "Default")
      (node (ref "IC1") (pin "23") (pinfunction "GPA2_23") (pintype "bidirectional"))
      (node (ref "U15") (pin "1") (pinfunction "G_1") (pintype "input"))
    )
    (net (code "32") (name "Net-(IC1-GPA3)") (class "Default")
      (node (ref "IC1") (pin "24") (pinfunction "GPA3_24") (pintype "bidirectional"))
      (node (ref "U14") (pin "1") (pinfunction "G_1") (pintype "input"))
    )
    (net (code "33") (name "Net-(IC1-GPB0)") (class "Default")
      (node (ref "IC1") (pin "1") (pinfunction "GPB0_1") (pintype "bidirectional"))
      (node (ref "U13") (pin "4") (pinfunction "~{MUTE}_4") (pintype "input"))
    )
    (net (code "34") (name "Net-(IC1-GPB1)") (class "Default")
      (node (ref "IC1") (pin "2") (pinfunction "GPB1_2") (pintype "bidirectional"))
      (node (ref "U8") (pin "4") (pinfunction "~{E}_4") (pintype "input"))
      (node (ref "U9") (pin "4") (pinfunction "~{E}_4") (pintype "input"))
    )
    (net (code "35") (name "Net-(IC1-GPB2)") (class "Default")
      (node (ref "IC1") (pin "3") (pinfunction "GPB2_3") (pintype "bidirectional"))
      (node (ref "U10") (pin "4") (pinfunction "~{E}_4") (pintype "input"))
      (node (ref "U11") (pin "4") (pinfunction "~{E}_4") (pintype "input"))
    )
    (net (code "36") (name "Net-(IC1-GPB3)") (class "Default")
      (node (ref "IC1") (pin "4") (pinfunction "GPB3_4") (pintype "bidirectional"))
      (node (ref "U$6") (pin "4") (pinfunction "~{RSTB}_4") (pintype "bidirectional"))
    )
    (net (code "37") (name "Net-(IC1-GPB4)") (class "Default")
      (node (ref "IC1") (pin "5") (pinfunction "GPB4_5") (pintype "bidirectional"))
      (node (ref "U1") (pin "1") (pinfunction "WDI_1") (pintype "input"))
    )
    (net (code "38") (name "Net-(IC1-SCL)") (class "Default")
      (node (ref "IC1") (pin "12") (pinfunction "SCL_12") (pintype "input"))
      (node (ref "R3") (pin "1") (pinfunction "1_1") (pintype "passive"))
      (node (ref "TP8") (pin "TP") (pinfunction "TP_TP") (pintype "input"))
      (node (ref "U2") (pin "1") (pinfunction "B2_1") (pintype "bidirectional"))
      (node (ref "U3") (pin "7") (pinfunction "SY_7") (pintype "input"))
      (node (ref "U5") (pin "6") (pinfunction "SCL_6") (pintype "input"))
    )
    (net (code "39") (name "Net-(IC1-SDA)") (class "Default")
      (node (ref "IC1") (pin "13") (pinfunction "SDA_13") (pintype "bidirectional"))
      (node (ref "R2") (pin "1") (pinfunction "1_1") (pintype "passive"))
      (node (ref "TP9") (pin "TP") (pinfunction "TP_TP") (pintype "input"))
      (node (ref "U2") (pin "8") (pinfunction "B1_8") (pintype "bidirectional"))
      (node (ref "U3") (pin "1") (pinfunction "SX_1") (pintype "input"))
      (node (ref "U5") (pin "5") (pinfunction "SDA_5") (pintype "bidirectional"))
    )
    (net (code "40") (name "Net-(K1A--)") (class "Default")
      (node (ref "D8") (pin "A") (pinfunction "A_A") (pintype "passive"))
      (node (ref "K1") (pin "8") (pinfunction "-_8") (pintype "passive"))
      (node (ref "U14") (pin "3") (pinfunction "D_3") (pintype "output"))
    )
    (net (code "41") (name "Net-(K1B-P)") (class "Default")
      (node (ref "K1") (pin "3") (pinfunction "P_3") (pintype "passive"))
      (node (ref "X5") (pin "P$2") (pinfunction "2_P$2") (pintype "passive"))
    )
    (net (code "42") (name "Net-(K1B-S)") (class "Default")
      (node (ref "K1") (pin "4") (pinfunction "S_4") (pintype "passive"))
      (node (ref "X5") (pin "P$1") (pinfunction "1_P$1") (pintype "passive"))
    )
    (net (code "43") (name "Net-(K2A--)") (class "Default")
      (node (ref "D9") (pin "A") (pinfunction "A_A") (pintype "passive"))
      (node (ref "K2") (pin "8") (pinfunction "-_8") (pintype "passive"))
      (node (ref "U15") (pin "3") (pinfunction "D_3") (pintype "output"))
    )
    (net (code "44") (name "Net-(K2B-P)") (class "Default")
      (node (ref "K2") (pin "3") (pinfunction "P_3") (pintype "passive"))
      (node (ref "X5") (pin "P$4") (pinfunction "4_P$4") (pintype "passive"))
    )
    (net (code "45") (name "Net-(K2B-S)") (class "Default")
      (node (ref "K2") (pin "4") (pinfunction "S_4") (pintype "passive"))
      (node (ref "X5") (pin "P$3") (pinfunction "3_P$3") (pintype "passive"))
    )
    (net (code "46") (name "Net-(K3A--)") (class "Default")
      (node (ref "D10") (pin "A") (pinfunction "A_A") (pintype "passive"))
      (node (ref "K3") (pin "8") (pinfunction "-_8") (pintype "passive"))
      (node (ref "U16") (pin "3") (pinfunction "D_3") (pintype "output"))
    )
    (net (code "47") (name "Net-(K3B-P)") (class "Default")
      (node (ref "K3") (pin "3") (pinfunction "P_3") (pintype "passive"))
      (node (ref "X5") (pin "P$6") (pinfunction "6_P$6") (pintype "passive"))
    )
    (net (code "48") (name "Net-(K3B-S)") (class "Default")
      (node (ref "K3") (pin "4") (pinfunction "S_4") (pintype "passive"))
      (node (ref "X5") (pin "P$5") (pinfunction "5_P$5") (pintype "passive"))
    )
    (net (code "49") (name "Net-(K4A--)") (class "Default")
      (node (ref "D11") (pin "A") (pinfunction "A_A") (pintype "passive"))
      (node (ref "K4") (pin "8") (pinfunction "-_8") (pintype "passive"))
      (node (ref "U17") (pin "3") (pinfunction "D_3") (pintype "output"))
    )
    (net (code "50") (name "Net-(K4B-P)") (class "Default")
      (node (ref "K4") (pin "3") (pinfunction "P_3") (pintype "passive"))
      (node (ref "X5") (pin "P$8") (pinfunction "8_P$8") (pintype "passive"))
    )
    (net (code "51") (name "Net-(K4B-S)") (class "Default")
      (node (ref "K4") (pin "4") (pinfunction "S_4") (pintype "passive"))
      (node (ref "X5") (pin "P$7") (pinfunction "7_P$7") (pintype "passive"))
    )
    (net (code "52") (name "Net-(LED1-PadA)") (class "Default")
      (node (ref "LED1") (pin "A") (pinfunction "A_A") (pintype "passive"))
      (node (ref "R1") (pin "1") (pinfunction "1_1") (pintype "passive"))
    )
    (net (code "53") (name "Net-(R6-Pad2)") (class "Default")
      (node (ref "R6") (pin "2") (pinfunction "2_2") (pintype "passive"))
      (node (ref "U$11") (pin "LEFT") (pinfunction "LEFT_LEFT") (pintype "passive"))
    )
    (net (code "54") (name "Net-(R7-Pad2)") (class "Default")
      (node (ref "R7") (pin "2") (pinfunction "2_2") (pintype "passive"))
      (node (ref "U$11") (pin "RIGHT") (pinfunction "RIGHT_RIGHT") (pintype "passive"))
    )
    (net (code "55") (name "Net-(R12-E)") (class "Default")
      (node (ref "R12") (pin "1") (pinfunction "E_1") (pintype "passive"))
      (node (ref "R13") (pin "2") (pinfunction "2_2") (pintype "passive"))
    )
    (net (code "56") (name "Net-(SPI-OE)") (class "Default")
      (node (ref "CON1") (pin "1") (pinfunction "1_1") (pintype "passive"))
      (node (ref "R14") (pin "2") (pinfunction "2_2") (pintype "passive"))
      (node (ref "SPI") (pin "1") (pinfunction "VCCA_1") (pintype "bidirectional"))
      (node (ref "SPI") (pin "8") (pinfunction "OE_8") (pintype "bidirectional"))
      (node (ref "U2") (pin "3") (pinfunction "VCCA_3") (pintype "power_in"))
      (node (ref "U2") (pin "6") (pinfunction "OE_6") (pintype "input"))
    )
    (net (code "57") (name "Net-(U$2-1)") (class "Default")
      (node (ref "U$2") (pin "2") (pinfunction "1_2") (pintype "passive"))
      (node (ref "U$6") (pin "15") (pinfunction "XTALI_15") (pintype "bidirectional"))
    )
    (net (code "58") (name "Net-(U$2-2)") (class "Default")
      (node (ref "U$2") (pin "4") (pinfunction "2_4") (pintype "passive"))
      (node (ref "U$6") (pin "16") (pinfunction "XTALO_16") (pintype "bidirectional"))
    )
    (net (code "59") (name "Net-(U$6-ABYP)") (class "Default")
      (node (ref "C12") (pin "2") (pinfunction "2_2") (pintype "passive"))
      (node (ref "C22") (pin "2") (pinfunction "2_2") (pintype "passive"))
      (node (ref "U$6") (pin "13") (pinfunction "ABYP_13") (pintype "bidirectional"))
    )
    (net (code "60") (name "Net-(U$6-DACREF)") (class "Default")
      (node (ref "C23") (pin "2") (pinfunction "2_2") (pintype "passive"))
      (node (ref "U$6") (pin "17") (pinfunction "DACREF_17") (pintype "bidirectional"))
    )
    (net (code "61") (name "Net-(U$6-DBYP)") (class "Default")
      (node (ref "C11") (pin "2") (pinfunction "2_2") (pintype "passive"))
      (node (ref "C13") (pin "2") (pinfunction "2_2") (pintype "passive"))
      (node (ref "C26") (pin "2") (pinfunction "2_2") (pintype "passive"))
      (node (ref "C27") (pin "2") (pinfunction "2_2") (pintype "passive"))
      (node (ref "C28") (pin "1") (pinfunction "1_1") (pintype "passive"))
      (node (ref "C29") (pin "1") (pinfunction "1_1") (pintype "passive"))
      (node (ref "U$6") (pin "36") (pinfunction "DBYP_36") (pintype "bidirectional"))
    )
    (net (code "62") (name "Net-(U$6-LOUT)") (class "Default")
      (node (ref "C25") (pin "2") (pinfunction "2_2") (pintype "passive"))
      (node (ref "TP3") (pin "TP") (pinfunction "TP_TP") (pintype "input"))
      (node (ref "U$6") (pin "18") (pinfunction "LOUT_18") (pintype "bidirectional"))
      (node (ref "U8") (pin "1") (pinfunction "Y_1") (pintype "bidirectional"))
    )
    (net (code "63") (name "Net-(U$6-ROUT)") (class "Default")
      (node (ref "C24") (pin "2") (pinfunction "2_2") (pintype "passive"))
      (node (ref "TP2") (pin "TP") (pinfunction "TP_TP") (pintype "input"))
      (node (ref "U$6") (pin "19") (pinfunction "ROUT_19") (pintype "bidirectional"))
      (node (ref "U9") (pin "1") (pinfunction "Y_1") (pintype "bidirectional"))
    )
    (net (code "64") (name "Net-(U$6-VHFI)") (class "Default")
      (node (ref "U$1") (pin "2") (pinfunction "2_2") (pintype "passive"))
      (node (ref "U$4") (pin "2") (pinfunction "2_2") (pintype "passive"))
      (node (ref "U$5") (pin "2") (pinfunction "2_2") (pintype "passive"))
      (node (ref "U$6") (pin "10") (pinfunction "VHFI_10") (pintype "bidirectional"))
    )
    (net (code "65") (name "Net-(U$6-VHFSW)") (class "Default")
      (node (ref "U$5") (pin "1") (pinfunction "1_1") (pintype "passive"))
      (node (ref "U$6") (pin "11") (pinfunction "VHFSW_11") (pintype "bidirectional"))
    )
    (net (code "66") (name "Net-(U$7-BYP)") (class "Default")
      (node (ref "C6") (pin "1") (pinfunction "1_1") (pintype "passive"))
      (node (ref "U$7") (pin "4") (pinfunction "BYP_4") (pintype "bidirectional"))
    )
    (net (code "67") (name "Net-(U$8-BYP)") (class "Default")
      (node (ref "C15") (pin "1") (pinfunction "1_1") (pintype "passive"))
      (node (ref "U$8") (pin "4") (pinfunction "BYP_4") (pintype "bidirectional"))
    )
    (net (code "68") (name "Net-(U$9-BYP)") (class "Default")
      (node (ref "C30") (pin "1") (pinfunction "1_1") (pintype "passive"))
      (node (ref "U$9") (pin "4") (pinfunction "BYP_4") (pintype "bidirectional"))
    )
    (net (code "69") (name "Net-(U$10-BYP)") (class "Default")
      (node (ref "C7") (pin "1") (pinfunction "1_1") (pintype "passive"))
      (node (ref "U$10") (pin "4") (pinfunction "BYP_4") (pintype "bidirectional"))
    )
    (net (code "70") (name "Net-(U1-~{WDO})") (class "Default")
      (node (ref "JP1") (pin "2") (pinfunction "2_2") (pintype "passive"))
      (node (ref "U1") (pin "7") (pinfunction "~{WDO}_7") (pintype "output"))
    )
    (net (code "71") (name "Net-(U2-A1)") (class "Default")
      (node (ref "CON1") (pin "3") (pinfunction "3_3") (pintype "passive"))
      (node (ref "U2") (pin "5") (pinfunction "A1_5") (pintype "bidirectional"))
    )
    (net (code "72") (name "Net-(U2-A2)") (class "Default")
      (node (ref "CON1") (pin "5") (pinfunction "5_5") (pintype "passive"))
      (node (ref "U2") (pin "4") (pinfunction "A2_4") (pintype "bidirectional"))
    )
    (net (code "73") (name "Net-(U5-VBAT)") (class "Default")
      (node (ref "B1") (pin "+") (pinfunction "+_+") (pintype "passive"))
      (node (ref "U5") (pin "3") (pinfunction "VBAT_3") (pintype "power_in"))
    )
    (net (code "74") (name "Net-(U5-X1)") (class "Default")
      (node (ref "Q1") (pin "1") (pinfunction "1_1") (pintype "passive"))
      (node (ref "U5") (pin "1") (pinfunction "X1_1") (pintype "input"))
    )
    (net (code "75") (name "Net-(U5-X2)") (class "Default")
      (node (ref "Q1") (pin "2") (pinfunction "2_2") (pintype "passive"))
      (node (ref "U5") (pin "2") (pinfunction "X2_2") (pintype "output"))
    )
    (net (code "76") (name "Net-(U10-Y)") (class "Default")
      (node (ref "C9") (pin "2") (pinfunction "2_2") (pintype "passive"))
      (node (ref "D6") (pin "P$2") (pinfunction "P$2_P$2") (pintype "bidirectional"))
      (node (ref "R8") (pin "2") (pinfunction "2_2") (pintype "passive"))
      (node (ref "R9") (pin "1") (pinfunction "1_1") (pintype "passive"))
      (node (ref "U10") (pin "1") (pinfunction "Y_1") (pintype "bidirectional"))
    )
    (net (code "77") (name "Net-(U10-Z)") (class "Default")
      (node (ref "C16") (pin "1") (pinfunction "1_1") (pintype "passive"))
      (node (ref "TP4") (pin "TP") (pinfunction "TP_TP") (pintype "input"))
      (node (ref "U10") (pin "2") (pinfunction "Z_2") (pintype "bidirectional"))
      (node (ref "U8") (pin "2") (pinfunction "Z_2") (pintype "bidirectional"))
    )
    (net (code "78") (name "Net-(U11-Y)") (class "Default")
      (node (ref "C10") (pin "2") (pinfunction "2_2") (pintype "passive"))
      (node (ref "D7") (pin "P$2") (pinfunction "P$2_P$2") (pintype "bidirectional"))
      (node (ref "R10") (pin "2") (pinfunction "2_2") (pintype "passive"))
      (node (ref "R11") (pin "1") (pinfunction "1_1") (pintype "passive"))
      (node (ref "U11") (pin "1") (pinfunction "Y_1") (pintype "bidirectional"))
    )
    (net (code "79") (name "Net-(U11-Z)") (class "Default")
      (node (ref "C17") (pin "2") (pinfunction "2_2") (pintype "passive"))
      (node (ref "TP5") (pin "TP") (pinfunction "TP_TP") (pintype "input"))
      (node (ref "U11") (pin "2") (pinfunction "Z_2") (pintype "bidirectional"))
      (node (ref "U9") (pin "2") (pinfunction "Z_2") (pintype "bidirectional"))
    )
    (net (code "80") (name "Net-(U13--IN_L)") (class "Default")
      (node (ref "C16") (pin "2") (pinfunction "2_2") (pintype "passive"))
      (node (ref "U13") (pin "1") (pinfunction "-IN_L_1") (pintype "input"))
    )
    (net (code "81") (name "Net-(U13--IN_R)") (class "Default")
      (node (ref "C17") (pin "1") (pinfunction "1_1") (pintype "passive"))
      (node (ref "U13") (pin "14") (pinfunction "-IN_R_14") (pintype "input"))
    )
    (net (code "82") (name "Net-(U13-CN)") (class "Default")
      (node (ref "C19") (pin "1") (pinfunction "1_1") (pintype "passive"))
      (node (ref "U13") (pin "6") (pinfunction "CN_6") (pintype "bidirectional"))
    )
    (net (code "83") (name "Net-(U13-CP)") (class "Default")
      (node (ref "C19") (pin "2") (pinfunction "2_2") (pintype "passive"))
      (node (ref "U13") (pin "9") (pinfunction "CP_9") (pintype "bidirectional"))
    )
    (net (code "84") (name "Net-(U13-GAIN)") (class "Default")
      (node (ref "R13") (pin "1") (pinfunction "1_1") (pintype "passive"))
      (node (ref "U13") (pin "12") (pinfunction "GAIN_12") (pintype "input"))
    )
    (net (code "85") (name "Net-(U13-OUT_L)") (class "Default")
      (node (ref "U$12") (pin "LEFT") (pinfunction "LEFT_LEFT") (pintype "passive"))
      (node (ref "U13") (pin "2") (pinfunction "OUT_L_2") (pintype "output"))
    )
    (net (code "86") (name "Net-(U13-OUT_R)") (class "Default")
      (node (ref "U$12") (pin "RIGHT") (pinfunction "RIGHT_RIGHT") (pintype "passive"))
      (node (ref "U13") (pin "13") (pinfunction "OUT_R_13") (pintype "output"))
    )
    (net (code "87") (name "Net-(U13-VSS)") (class "Default")
      (node (ref "C21") (pin "2") (pinfunction "2_2") (pintype "passive"))
      (node (ref "U13") (pin "5") (pinfunction "VSS_5") (pintype "power_in"))
    )
    (net (code "88") (name "Net-(X2-2)") (class "Default")
      (node (ref "D1") (pin "A") (pinfunction "A_A") (pintype "passive"))
      (node (ref "X2") (pin "P$2") (pinfunction "2_P$2") (pintype "passive"))
    )
    (net (code "89") (name "VCC") (class "Default")
      (node (ref "C2") (pin "1") (pinfunction "1_1") (pintype "passive"))
      (node (ref "D1") (pin "C") (pinfunction "C_C") (pintype "passive"))
      (node (ref "D10") (pin "C") (pinfunction "C_C") (pintype "passive"))
      (node (ref "D11") (pin "C") (pinfunction "C_C") (pintype "passive"))
      (node (ref "D8") (pin "C") (pinfunction "C_C") (pintype "passive"))
      (node (ref "D9") (pin "C") (pinfunction "C_C") (pintype "passive"))
      (node (ref "IC2") (pin "1") (pinfunction "VI_1") (pintype "input"))
      (node (ref "K1") (pin "1") (pinfunction "+_1") (pintype "passive"))
      (node (ref "K2") (pin "1") (pinfunction "+_1") (pintype "passive"))
      (node (ref "K3") (pin "1") (pinfunction "+_1") (pintype "passive"))
      (node (ref "K4") (pin "1") (pinfunction "+_1") (pintype "passive"))
      (node (ref "R1") (pin "2") (pinfunction "2_2") (pintype "passive"))
      (node (ref "R4") (pin "2") (pinfunction "2_2") (pintype "passive"))
      (node (ref "R5") (pin "2") (pinfunction "2_2") (pintype "passive"))
    )
    (net (code "90") (name "unconnected-(B1-+-Pad+@1)") (class "Default")
      (node (ref "B1") (pin "+@1") (pinfunction "+_+@1") (pintype "passive"))
    )
    (net (code "91") (name "unconnected-(CON1-Pad7)") (class "Default")
      (node (ref "CON1") (pin "7") (pinfunction "7_7") (pintype "passive"))
    )
    (net (code "92") (name "unconnected-(CON1-Pad8)") (class "Default")
      (node (ref "CON1") (pin "8") (pinfunction "8_8") (pintype "passive"))
    )
    (net (code "93") (name "unconnected-(CON1-Pad10)") (class "Default")
      (node (ref "CON1") (pin "10") (pinfunction "10_10") (pintype "passive"))
    )
    (net (code "94") (name "unconnected-(CON1-Pad11)") (class "Default")
      (node (ref "CON1") (pin "11") (pinfunction "11_11") (pintype "passive"))
    )
    (net (code "95") (name "unconnected-(CON1-Pad12)") (class "Default")
      (node (ref "CON1") (pin "12") (pinfunction "12_12") (pintype "passive"))
    )
    (net (code "96") (name "unconnected-(CON1-Pad13)") (class "Default")
      (node (ref "CON1") (pin "13") (pinfunction "13_13") (pintype "passive"))
    )
    (net (code "97") (name "unconnected-(CON1-Pad15)") (class "Default")
      (node (ref "CON1") (pin "15") (pinfunction "15_15") (pintype "passive"))
    )
    (net (code "98") (name "unconnected-(CON1-Pad16)") (class "Default")
      (node (ref "CON1") (pin "16") (pinfunction "16_16") (pintype "passive"))
    )
    (net (code "99") (name "unconnected-(CON1-Pad17)") (class "Default")
      (node (ref "CON1") (pin "17") (pinfunction "17_17") (pintype "passive"))
    )
    (net (code "100") (name "unconnected-(CON1-Pad18)") (class "Default")
      (node (ref "CON1") (pin "18") (pinfunction "18_18") (pintype "passive"))
    )
    (net (code "101") (name "unconnected-(CON1-Pad22)") (class "Default")
      (node (ref "CON1") (pin "22") (pinfunction "22_22") (pintype "passive"))
    )
    (net (code "102") (name "unconnected-(CON1-Pad26)") (class "Default")
      (node (ref "CON1") (pin "26") (pinfunction "26_26") (pintype "passive"))
    )
    (net (code "103") (name "unconnected-(IC1-GPA4-Pad25)") (class "Default")
      (node (ref "IC1") (pin "25") (pinfunction "GPA4_25") (pintype "bidirectional"))
    )
    (net (code "104") (name "unconnected-(IC1-GPA5-Pad26)") (class "Default")
      (node (ref "IC1") (pin "26") (pinfunction "GPA5_26") (pintype "bidirectional"))
    )
    (net (code "105") (name "unconnected-(IC1-GPA6-Pad27)") (class "Default")
      (node (ref "IC1") (pin "27") (pinfunction "GPA6_27") (pintype "bidirectional"))
    )
    (net (code "106") (name "unconnected-(IC1-GPA7-Pad28)") (class "Default")
      (node (ref "IC1") (pin "28") (pinfunction "GPA7_28") (pintype "bidirectional"))
    )
    (net (code "107") (name "unconnected-(IC1-GPB5-Pad6)") (class "Default")
      (node (ref "IC1") (pin "6") (pinfunction "GPB5_6") (pintype "bidirectional"))
    )
    (net (code "108") (name "unconnected-(IC1-GPB6-Pad7)") (class "Default")
      (node (ref "IC1") (pin "7") (pinfunction "GPB6_7") (pintype "bidirectional"))
    )
    (net (code "109") (name "unconnected-(IC1-GPB7-Pad8)") (class "Default")
      (node (ref "IC1") (pin "8") (pinfunction "GPB7_8") (pintype "bidirectional"))
    )
    (net (code "110") (name "unconnected-(IC1-INTA-Pad20)") (class "Default")
      (node (ref "IC1") (pin "20") (pinfunction "INTA_20") (pintype "output"))
    )
    (net (code "111") (name "unconnected-(IC1-INTB-Pad19)") (class "Default")
      (node (ref "IC1") (pin "19") (pinfunction "INTB_19") (pintype "output"))
    )
    (net (code "112") (name "unconnected-(K1B-O-Pad2)") (class "Default")
      (node (ref "K1") (pin "2") (pinfunction "O_2") (pintype "passive"))
    )
    (net (code "113") (name "unconnected-(K1C-O-Pad7)") (class "Default")
      (node (ref "K1") (pin "7") (pinfunction "O_7") (pintype "passive"))
    )
    (net (code "114") (name "unconnected-(K1C-P-Pad6)") (class "Default")
      (node (ref "K1") (pin "6") (pinfunction "P_6") (pintype "passive"))
    )
    (net (code "115") (name "unconnected-(K1C-S-Pad5)") (class "Default")
      (node (ref "K1") (pin "5") (pinfunction "S_5") (pintype "passive"))
    )
    (net (code "116") (name "unconnected-(K2B-O-Pad2)") (class "Default")
      (node (ref "K2") (pin "2") (pinfunction "O_2") (pintype "passive"))
    )
    (net (code "117") (name "unconnected-(K2C-O-Pad7)") (class "Default")
      (node (ref "K2") (pin "7") (pinfunction "O_7") (pintype "passive"))
    )
    (net (code "118") (name "unconnected-(K2C-P-Pad6)") (class "Default")
      (node (ref "K2") (pin "6") (pinfunction "P_6") (pintype "passive"))
    )
    (net (code "119") (name "unconnected-(K2C-S-Pad5)") (class "Default")
      (node (ref "K2") (pin "5") (pinfunction "S_5") (pintype "passive"))
    )
    (net (code "120") (name "unconnected-(K3B-O-Pad2)") (class "Default")
      (node (ref "K3") (pin "2") (pinfunction "O_2") (pintype "passive"))
    )
    (net (code "121") (name "unconnected-(K3C-O-Pad7)") (class "Default")
      (node (ref "K3") (pin "7") (pinfunction "O_7") (pintype "passive"))
    )
    (net (code "122") (name "unconnected-(K3C-P-Pad6)") (class "Default")
      (node (ref "K3") (pin "6") (pinfunction "P_6") (pintype "passive"))
    )
    (net (code "123") (name "unconnected-(K3C-S-Pad5)") (class "Default")
      (node (ref "K3") (pin "5") (pinfunction "S_5") (pintype "passive"))
    )
    (net (code "124") (name "unconnected-(K4B-O-Pad2)") (class "Default")
      (node (ref "K4") (pin "2") (pinfunction "O_2") (pintype "passive"))
    )
    (net (code "125") (name "unconnected-(K4C-O-Pad7)") (class "Default")
      (node (ref "K4") (pin "7") (pinfunction "O_7") (pintype "passive"))
    )
    (net (code "126") (name "unconnected-(K4C-P-Pad6)") (class "Default")
      (node (ref "K4") (pin "6") (pinfunction "P_6") (pintype "passive"))
    )
    (net (code "127") (name "unconnected-(K4C-S-Pad5)") (class "Default")
      (node (ref "K4") (pin "5") (pinfunction "S_5") (pintype "passive"))
    )
    (net (code "128") (name "unconnected-(R12-A-Pad3)") (class "Default")
      (node (ref "R12") (pin "3") (pinfunction "A_3") (pintype "passive"))
    )
    (net (code "129") (name "unconnected-(U$6-DCLK-Pad27)") (class "Default")
      (node (ref "U$6") (pin "27") (pinfunction "DCLK_27") (pintype "bidirectional"))
    )
    (net (code "130") (name "unconnected-(U$6-DFS-Pad28)") (class "Default")
      (node (ref "U$6") (pin "28") (pinfunction "DFS_28") (pintype "bidirectional"))
    )
    (net (code "131") (name "unconnected-(U$6-DOUT-Pad33)") (class "Default")
      (node (ref "U$6") (pin "33") (pinfunction "DOUT_33") (pintype "bidirectional"))
    )
    (net (code "132") (name "unconnected-(U$6-NC1-Pad14)") (class "Default")
      (node (ref "U$6") (pin "14") (pinfunction "NC1_14") (pintype "no_connect"))
    )
    (net (code "133") (name "unconnected-(U$6-NC2-Pad20)") (class "Default")
      (node (ref "U$6") (pin "20") (pinfunction "NC2_20") (pintype "no_connect"))
    )
    (net (code "134") (name "unconnected-(U$6-NC3-Pad21)") (class "Default")
      (node (ref "U$6") (pin "21") (pinfunction "NC3_21") (pintype "no_connect"))
    )
    (net (code "135") (name "unconnected-(U$6-NC4-Pad22)") (class "Default")
      (node (ref "U$6") (pin "22") (pinfunction "NC4_22") (pintype "no_connect"))
    )
    (net (code "136") (name "unconnected-(U$6-NC5-Pad23)") (class "Default")
      (node (ref "U$6") (pin "23") (pinfunction "NC5_23") (pintype "no_connect"))
    )
    (net (code "137") (name "unconnected-(U$6-NC6-Pad24)") (class "Default")
      (node (ref "U$6") (pin "24") (pinfunction "NC6_24") (pintype "no_connect"))
    )
    (net (code "138") (name "unconnected-(U$6-NC7-Pad25)") (class "Default")
      (node (ref "U$6") (pin "25") (pinfunction "NC7_25") (pintype "no_connect"))
    )
    (net (code "139") (name "unconnected-(U$6-NC8-Pad26)") (class "Default")
      (node (ref "U$6") (pin "26") (pinfunction "NC8_26") (pintype "no_connect"))
    )
    (net (code "140") (name "unconnected-(U$6-NC9-Pad38)") (class "Default")
      (node (ref "U$6") (pin "38") (pinfunction "NC9_38") (pintype "no_connect"))
    )
    (net (code "141") (name "unconnected-(U$6-NC10-Pad43)") (class "Default")
      (node (ref "U$6") (pin "43") (pinfunction "NC10_43") (pintype "no_connect"))
    )
    (net (code "142") (name "unconnected-(U$6-NC11-Pad44)") (class "Default")
      (node (ref "U$6") (pin "44") (pinfunction "NC11_44") (pintype "no_connect"))
    )
    (net (code "143") (name "unconnected-(U$6-NC12-Pad45)") (class "Default")
      (node (ref "U$6") (pin "45") (pinfunction "NC12_45") (pintype "no_connect"))
    )
    (net (code "144") (name "unconnected-(U$6-NC13-Pad46)") (class "Default")
      (node (ref "U$6") (pin "46") (pinfunction "NC13_46") (pintype "no_connect"))
    )
    (net (code "145") (name "unconnected-(U$6-~{INTB}-Pad3)") (class "Default")
      (node (ref "U$6") (pin "3") (pinfunction "~{INTB}_3") (pintype "bidirectional"))
    )
    (net (code "146") (name "unconnected-(U1-N.C.-Pad3)") (class "Default")
      (node (ref "U1") (pin "3") (pinfunction "N.C._3") (pintype "no_connect"))
    )
    (net (code "147") (name "unconnected-(U5-SQW{slash}OUT-Pad8)") (class "Default")
      (node (ref "U5") (pin "8") (pinfunction "SQW/OUT_8") (pintype "output"))
    )
    (net (code "148") (name "unconnected-(U13-NC-Pad8)") (class "Default")
      (node (ref "U13") (pin "8") (pinfunction "NC_8") (pintype "no_connect"))
    )
    (net (code "149") (name "unconnected-(U13-NC_2-Pad7)") (class "Default")
      (node (ref "U13") (pin "7") (pinfunction "NC_2_7") (pintype "no_connect"))
    )
  )
)
